# RoboticArm3dPrinter.net
KiCad netlist of a schematic drawn in EAGLE
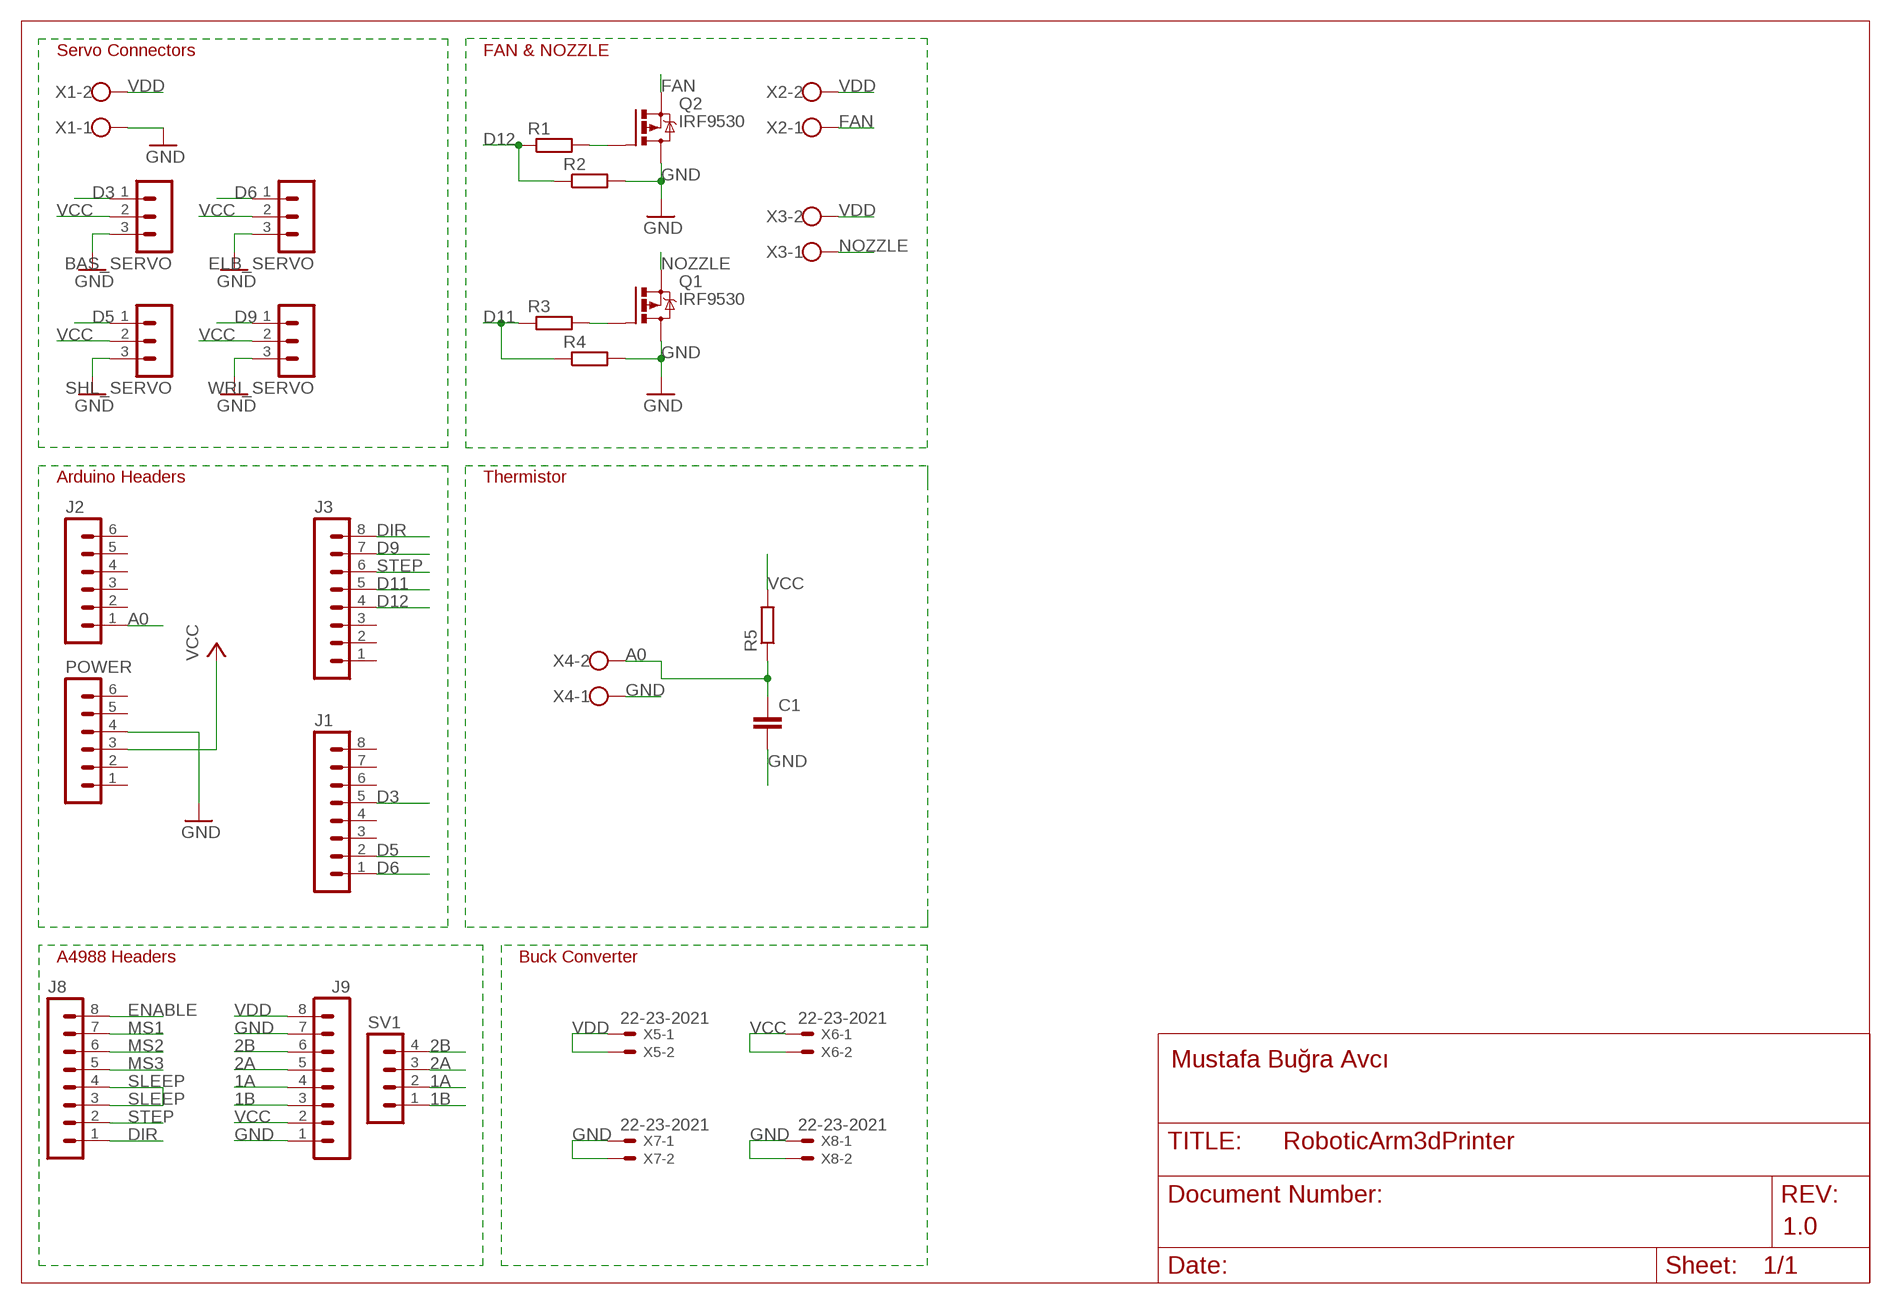
[diagram p0: schematic, sheet 1]

(export (version "E")
  (design (tool "Eeschema 10.0.6"))
  (components
    (comp (ref "BAS_SERVO")
      (value "MA03-1")
      (footprint "eagle-import:MA03-1")
      (libsource (lib "eagle-import") (part "MA03-1"))
    )
    (comp (ref "C1")
      (value "C5/2.5")
      (footprint "eagle-import:C5B2.5")
      (libsource (lib "eagle-import") (part "C5/2.5"))
    )
    (comp (ref "ELB_SERVO")
      (value "MA03-1")
      (footprint "eagle-import:MA03-1")
      (libsource (lib "eagle-import") (part "MA03-1"))
    )
    (comp (ref "J1")
      (value "MA08-1")
      (footprint "eagle-import:MA08-1")
      (libsource (lib "eagle-import") (part "MA08-1"))
    )
    (comp (ref "J2")
      (value "MA06-1")
      (footprint "eagle-import:MA06-1")
      (libsource (lib "eagle-import") (part "MA06-1"))
    )
    (comp (ref "J3")
      (value "MA08-1")
      (footprint "eagle-import:MA08-1")
      (libsource (lib "eagle-import") (part "MA08-1"))
    )
    (comp (ref "J8")
      (value "MA08-1")
      (footprint "eagle-import:MA08-1")
      (libsource (lib "eagle-import") (part "MA08-1"))
    )
    (comp (ref "J9")
      (value "MA08-1")
      (footprint "eagle-import:MA08-1")
      (libsource (lib "eagle-import") (part "MA08-1"))
    )
    (comp (ref "POWER")
      (value "MA06-1")
      (footprint "eagle-import:MA06-1")
      (libsource (lib "eagle-import") (part "MA06-1"))
    )
    (comp (ref "Q1")
      (value "IRF9530")
      (footprint "eagle-import:TO220BV")
      (libsource (lib "eagle-import") (part "IRF9530"))
    )
    (comp (ref "Q2")
      (value "IRF9530")
      (footprint "eagle-import:TO220BV")
      (libsource (lib "eagle-import") (part "IRF9530"))
    )
    (comp (ref "R1")
      (value "R-EU_0207/10")
      (footprint "eagle-import:0207_10")
      (libsource (lib "eagle-import") (part "R-EU_0207/10"))
    )
    (comp (ref "R2")
      (value "R-EU_0207/10")
      (footprint "eagle-import:0207_10")
      (libsource (lib "eagle-import") (part "R-EU_0207/10"))
    )
    (comp (ref "R3")
      (value "R-EU_0207/10")
      (footprint "eagle-import:0207_10")
      (libsource (lib "eagle-import") (part "R-EU_0207/10"))
    )
    (comp (ref "R4")
      (value "R-EU_0207/10")
      (footprint "eagle-import:0207_10")
      (libsource (lib "eagle-import") (part "R-EU_0207/10"))
    )
    (comp (ref "R5")
      (value "R-EU_0207/10")
      (footprint "eagle-import:0207_10")
      (libsource (lib "eagle-import") (part "R-EU_0207/10"))
    )
    (comp (ref "SHL_SERVO")
      (value "MA03-1")
      (footprint "eagle-import:MA03-1")
      (libsource (lib "eagle-import") (part "MA03-1"))
    )
    (comp (ref "SV1")
      (value "MA04-1")
      (footprint "eagle-import:MA04-1")
      (libsource (lib "eagle-import") (part "MA04-1"))
    )
    (comp (ref "WRI_SERVO")
      (value "MA03-1")
      (footprint "eagle-import:MA03-1")
      (libsource (lib "eagle-import") (part "MA03-1"))
    )
    (comp (ref "X1")
      (value "W237-102")
      (footprint "eagle-import:W237-102")
      (libsource (lib "eagle-import") (part "W237-102"))
    )
    (comp (ref "X2")
      (value "W237-102")
      (footprint "eagle-import:W237-102")
      (libsource (lib "eagle-import") (part "W237-102"))
    )
    (comp (ref "X3")
      (value "W237-102")
      (footprint "eagle-import:W237-102")
      (libsource (lib "eagle-import") (part "W237-102"))
    )
    (comp (ref "X4")
      (value "W237-102")
      (footprint "eagle-import:W237-102")
      (libsource (lib "eagle-import") (part "W237-102"))
    )
    (comp (ref "X5")
      (value "22-23-2021")
      (footprint "eagle-import:22-23-2021")
      (fields (field (name "MF") "MOLEX"))
      (libsource (lib "eagle-import") (part "22-23-2021"))
    )
    (comp (ref "X6")
      (value "22-23-2021")
      (footprint "eagle-import:22-23-2021")
      (fields (field (name "MF") "MOLEX"))
      (libsource (lib "eagle-import") (part "22-23-2021"))
    )
    (comp (ref "X7")
      (value "22-23-2021")
      (footprint "eagle-import:22-23-2021")
      (fields (field (name "MF") "MOLEX"))
      (libsource (lib "eagle-import") (part "22-23-2021"))
    )
    (comp (ref "X8")
      (value "22-23-2021")
      (footprint "eagle-import:22-23-2021")
      (fields (field (name "MF") "MOLEX"))
      (libsource (lib "eagle-import") (part "22-23-2021"))
    )
  )
  (nets
    (net (code "1") (name "/1A") (class "Default")
      (node (ref "J9") (pin "4") (pinfunction "4_4") (pintype "passive"))
      (node (ref "SV1") (pin "2") (pinfunction "2_2") (pintype "passive"))
    )
    (net (code "2") (name "/1B") (class "Default")
      (node (ref "J9") (pin "3") (pinfunction "3_3") (pintype "passive"))
      (node (ref "SV1") (pin "1") (pinfunction "1_1") (pintype "passive"))
    )
    (net (code "3") (name "/2A") (class "Default")
      (node (ref "J9") (pin "5") (pinfunction "5_5") (pintype "passive"))
      (node (ref "SV1") (pin "3") (pinfunction "3_3") (pintype "passive"))
    )
    (net (code "4") (name "/2B") (class "Default")
      (node (ref "J9") (pin "6") (pinfunction "6_6") (pintype "passive"))
      (node (ref "SV1") (pin "4") (pinfunction "4_4") (pintype "passive"))
    )
    (net (code "5") (name "/A0") (class "Default")
      (node (ref "C1") (pin "1") (pinfunction "1_1") (pintype "passive"))
      (node (ref "J2") (pin "1") (pinfunction "1_1") (pintype "passive"))
      (node (ref "R5") (pin "1") (pinfunction "1_1") (pintype "passive"))
      (node (ref "X4") (pin "2") (pinfunction "KL_2") (pintype "passive"))
    )
    (net (code "6") (name "/D3") (class "Default")
      (node (ref "BAS_SERVO") (pin "1") (pinfunction "1_1") (pintype "passive"))
      (node (ref "J1") (pin "5") (pinfunction "5_5") (pintype "passive"))
    )
    (net (code "7") (name "/D5") (class "Default")
      (node (ref "J1") (pin "2") (pinfunction "2_2") (pintype "passive"))
      (node (ref "SHL_SERVO") (pin "1") (pinfunction "1_1") (pintype "passive"))
    )
    (net (code "8") (name "/D6") (class "Default")
      (node (ref "ELB_SERVO") (pin "1") (pinfunction "1_1") (pintype "passive"))
      (node (ref "J1") (pin "1") (pinfunction "1_1") (pintype "passive"))
    )
    (net (code "9") (name "/D9") (class "Default")
      (node (ref "J3") (pin "7") (pinfunction "7_7") (pintype "passive"))
      (node (ref "WRI_SERVO") (pin "1") (pinfunction "1_1") (pintype "passive"))
    )
    (net (code "10") (name "/D11") (class "Default")
      (node (ref "J3") (pin "5") (pinfunction "5_5") (pintype "passive"))
      (node (ref "R3") (pin "1") (pinfunction "1_1") (pintype "passive"))
      (node (ref "R4") (pin "1") (pinfunction "1_1") (pintype "passive"))
    )
    (net (code "11") (name "/D12") (class "Default")
      (node (ref "J3") (pin "4") (pinfunction "4_4") (pintype "passive"))
      (node (ref "R1") (pin "1") (pinfunction "1_1") (pintype "passive"))
      (node (ref "R2") (pin "1") (pinfunction "1_1") (pintype "passive"))
    )
    (net (code "12") (name "/DIR") (class "Default")
      (node (ref "J3") (pin "8") (pinfunction "8_8") (pintype "passive"))
      (node (ref "J8") (pin "1") (pinfunction "1_1") (pintype "passive"))
    )
    (net (code "13") (name "/ENABLE") (class "Default")
      (node (ref "J8") (pin "8") (pinfunction "8_8") (pintype "passive"))
    )
    (net (code "14") (name "/FAN") (class "Default")
      (node (ref "Q2") (pin "S") (pinfunction "S_S") (pintype "passive"))
      (node (ref "X2") (pin "1") (pinfunction "KL_1") (pintype "passive"))
    )
    (net (code "15") (name "/MS1") (class "Default")
      (node (ref "J8") (pin "7") (pinfunction "7_7") (pintype "passive"))
    )
    (net (code "16") (name "/MS2") (class "Default")
      (node (ref "J8") (pin "6") (pinfunction "6_6") (pintype "passive"))
    )
    (net (code "17") (name "/MS3") (class "Default")
      (node (ref "J8") (pin "5") (pinfunction "5_5") (pintype "passive"))
    )
    (net (code "18") (name "/NOZZLE") (class "Default")
      (node (ref "Q1") (pin "S") (pinfunction "S_S") (pintype "passive"))
      (node (ref "X3") (pin "1") (pinfunction "KL_1") (pintype "passive"))
    )
    (net (code "19") (name "/SLEEP") (class "Default")
      (node (ref "J8") (pin "3") (pinfunction "3_3") (pintype "passive"))
      (node (ref "J8") (pin "4") (pinfunction "4_4") (pintype "passive"))
    )
    (net (code "20") (name "/STEP") (class "Default")
      (node (ref "J3") (pin "6") (pinfunction "6_6") (pintype "passive"))
      (node (ref "J8") (pin "2") (pinfunction "2_2") (pintype "passive"))
    )
    (net (code "21") (name "/VDD") (class "Default")
      (node (ref "J9") (pin "8") (pinfunction "8_8") (pintype "passive"))
      (node (ref "X1") (pin "2") (pinfunction "KL_2") (pintype "passive"))
      (node (ref "X2") (pin "2") (pinfunction "KL_2") (pintype "passive"))
      (node (ref "X3") (pin "2") (pinfunction "KL_2") (pintype "passive"))
      (node (ref "X5") (pin "1") (pinfunction "S_1") (pintype "passive"))
      (node (ref "X5") (pin "2") (pinfunction "S_2") (pintype "passive"))
    )
    (net (code "22") (name "GND") (class "Default")
      (node (ref "BAS_SERVO") (pin "3") (pinfunction "3_3") (pintype "passive"))
      (node (ref "C1") (pin "2") (pinfunction "2_2") (pintype "passive"))
      (node (ref "ELB_SERVO") (pin "3") (pinfunction "3_3") (pintype "passive"))
      (node (ref "J9") (pin "1") (pinfunction "1_1") (pintype "passive"))
      (node (ref "J9") (pin "7") (pinfunction "7_7") (pintype "passive"))
      (node (ref "POWER") (pin "4") (pinfunction "4_4") (pintype "passive"))
      (node (ref "Q1") (pin "D") (pinfunction "D_D") (pintype "passive"))
      (node (ref "Q2") (pin "D") (pinfunction "D_D") (pintype "passive"))
      (node (ref "R2") (pin "2") (pinfunction "2_2") (pintype "passive"))
      (node (ref "R4") (pin "2") (pinfunction "2_2") (pintype "passive"))
      (node (ref "SHL_SERVO") (pin "3") (pinfunction "3_3") (pintype "passive"))
      (node (ref "WRI_SERVO") (pin "3") (pinfunction "3_3") (pintype "passive"))
      (node (ref "X1") (pin "1") (pinfunction "KL_1") (pintype "passive"))
      (node (ref "X4") (pin "1") (pinfunction "KL_1") (pintype "passive"))
      (node (ref "X7") (pin "1") (pinfunction "S_1") (pintype "passive"))
      (node (ref "X7") (pin "2") (pinfunction "S_2") (pintype "passive"))
      (node (ref "X8") (pin "1") (pinfunction "S_1") (pintype "passive"))
      (node (ref "X8") (pin "2") (pinfunction "S_2") (pintype "passive"))
    )
    (net (code "23") (name "Net-(Q1-PadG)") (class "Default")
      (node (ref "Q1") (pin "G") (pinfunction "G_G") (pintype "passive"))
      (node (ref "R3") (pin "2") (pinfunction "2_2") (pintype "passive"))
    )
    (net (code "24") (name "Net-(Q2-PadG)") (class "Default")
      (node (ref "Q2") (pin "G") (pinfunction "G_G") (pintype "passive"))
      (node (ref "R1") (pin "2") (pinfunction "2_2") (pintype "passive"))
    )
    (net (code "25") (name "VCC") (class "Default")
      (node (ref "BAS_SERVO") (pin "2") (pinfunction "2_2") (pintype "passive"))
      (node (ref "ELB_SERVO") (pin "2") (pinfunction "2_2") (pintype "passive"))
      (node (ref "J9") (pin "2") (pinfunction "2_2") (pintype "passive"))
      (node (ref "POWER") (pin "3") (pinfunction "3_3") (pintype "passive"))
      (node (ref "R5") (pin "2") (pinfunction "2_2") (pintype "passive"))
      (node (ref "SHL_SERVO") (pin "2") (pinfunction "2_2") (pintype "passive"))
      (node (ref "WRI_SERVO") (pin "2") (pinfunction "2_2") (pintype "passive"))
      (node (ref "X6") (pin "1") (pinfunction "S_1") (pintype "passive"))
      (node (ref "X6") (pin "2") (pinfunction "S_2") (pintype "passive"))
    )
    (net (code "26") (name "unconnected-(J1-Pad3)") (class "Default")
      (node (ref "J1") (pin "3") (pinfunction "3_3") (pintype "passive"))
    )
    (net (code "27") (name "unconnected-(J1-Pad4)") (class "Default")
      (node (ref "J1") (pin "4") (pinfunction "4_4") (pintype "passive"))
    )
    (net (code "28") (name "unconnected-(J1-Pad6)") (class "Default")
      (node (ref "J1") (pin "6") (pinfunction "6_6") (pintype "passive"))
    )
    (net (code "29") (name "unconnected-(J1-Pad7)") (class "Default")
      (node (ref "J1") (pin "7") (pinfunction "7_7") (pintype "passive"))
    )
    (net (code "30") (name "unconnected-(J1-Pad8)") (class "Default")
      (node (ref "J1") (pin "8") (pinfunction "8_8") (pintype "passive"))
    )
    (net (code "31") (name "unconnected-(J2-Pad2)") (class "Default")
      (node (ref "J2") (pin "2") (pinfunction "2_2") (pintype "passive"))
    )
    (net (code "32") (name "unconnected-(J2-Pad3)") (class "Default")
      (node (ref "J2") (pin "3") (pinfunction "3_3") (pintype "passive"))
    )
    (net (code "33") (name "unconnected-(J2-Pad4)") (class "Default")
      (node (ref "J2") (pin "4") (pinfunction "4_4") (pintype "passive"))
    )
    (net (code "34") (name "unconnected-(J2-Pad5)") (class "Default")
      (node (ref "J2") (pin "5") (pinfunction "5_5") (pintype "passive"))
    )
    (net (code "35") (name "unconnected-(J2-Pad6)") (class "Default")
      (node (ref "J2") (pin "6") (pinfunction "6_6") (pintype "passive"))
    )
    (net (code "36") (name "unconnected-(J3-Pad1)") (class "Default")
      (node (ref "J3") (pin "1") (pinfunction "1_1") (pintype "passive"))
    )
    (net (code "37") (name "unconnected-(J3-Pad2)") (class "Default")
      (node (ref "J3") (pin "2") (pinfunction "2_2") (pintype "passive"))
    )
    (net (code "38") (name "unconnected-(J3-Pad3)") (class "Default")
      (node (ref "J3") (pin "3") (pinfunction "3_3") (pintype "passive"))
    )
    (net (code "39") (name "unconnected-(POWER-Pad1)") (class "Default")
      (node (ref "POWER") (pin "1") (pinfunction "1_1") (pintype "passive"))
    )
    (net (code "40") (name "unconnected-(POWER-Pad2)") (class "Default")
      (node (ref "POWER") (pin "2") (pinfunction "2_2") (pintype "passive"))
    )
    (net (code "41") (name "unconnected-(POWER-Pad5)") (class "Default")
      (node (ref "POWER") (pin "5") (pinfunction "5_5") (pintype "passive"))
    )
    (net (code "42") (name "unconnected-(POWER-Pad6)") (class "Default")
      (node (ref "POWER") (pin "6") (pinfunction "6_6") (pintype "passive"))
    )
  )
)
